# 8_ddr3_termination.net
KiCad netlist of a schematic drawn in Altium Designer
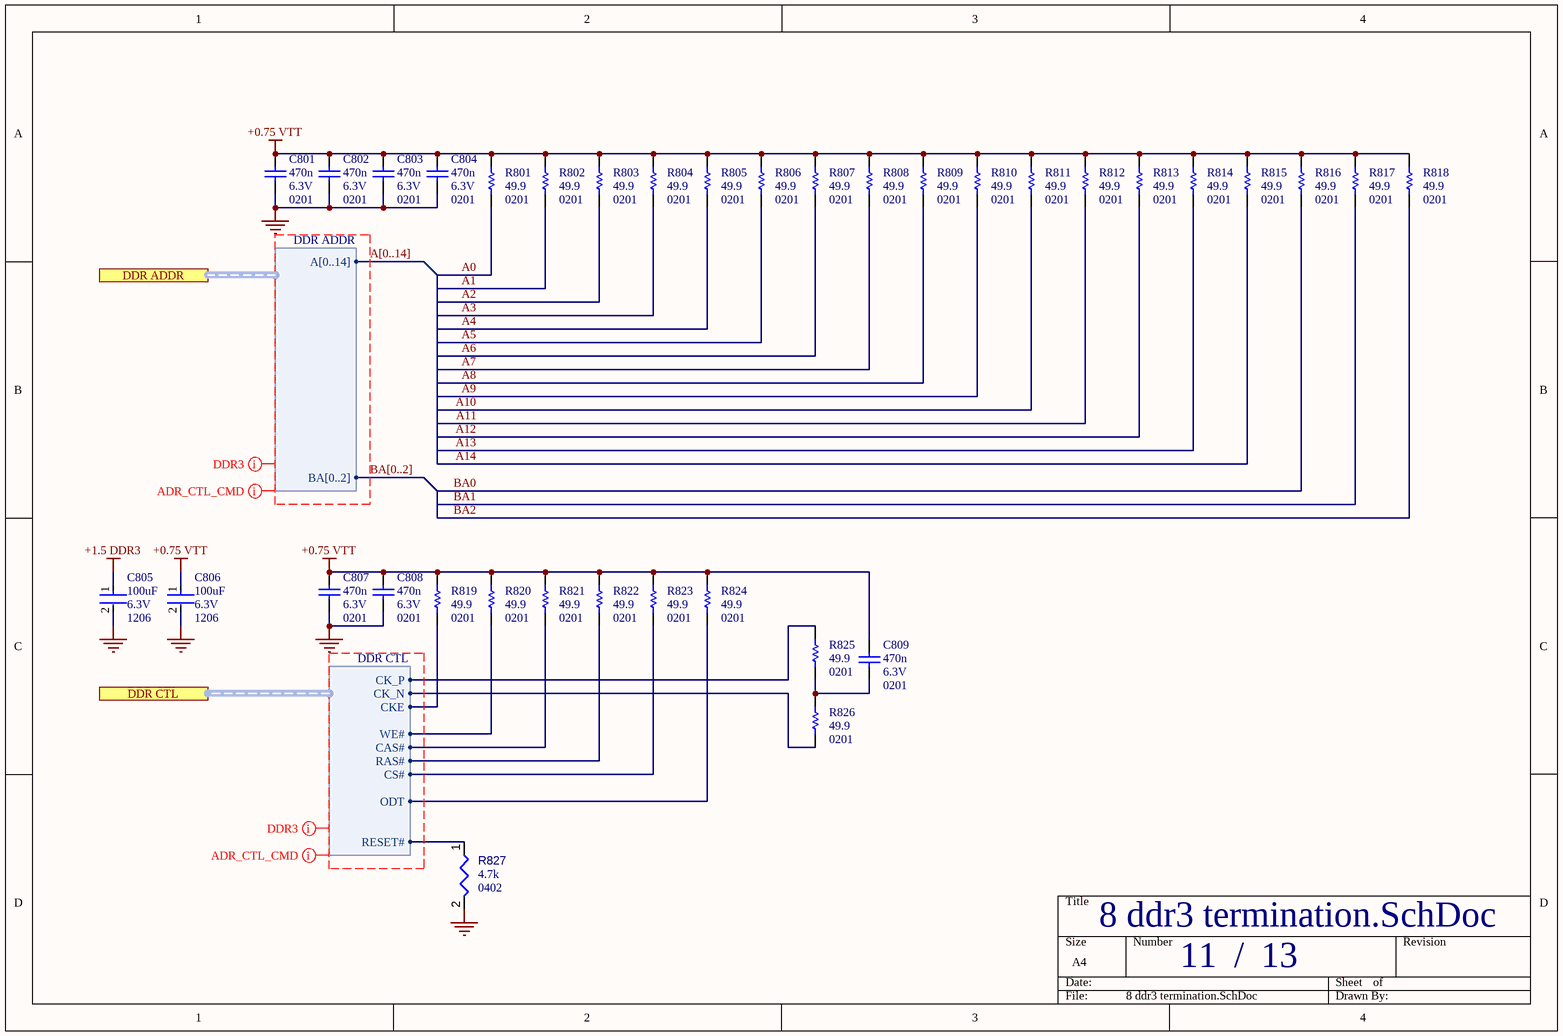
[diagram p0: 8 ddr3 termination.SchDoc]

(export (version "E")
  (design (tool "Eeschema 10.0.6"))
  (components
    (comp (ref "C801")
      (value "470n")
      (footprint "CAPC0603X33X15LL03T05")
      (fields
        (field (name "MANUFACTURER") "AVX Interconnect / Elco")
        (field (name "PART NUMBER") "02016D474KAT2A")
        (field (name "VOLTAGE RATING") "6.3V")
        (field (name "PACKAGE") "0201")
      )
      (libsource (lib "Altium Content Vault") (part "CAP"))
    )
    (comp (ref "C802")
      (value "470n")
      (footprint "CAPC0603X33X15LL03T05")
      (fields
        (field (name "MANUFACTURER") "AVX Interconnect / Elco")
        (field (name "PART NUMBER") "02016D474KAT2A")
        (field (name "VOLTAGE RATING") "6.3V")
        (field (name "PACKAGE") "0201")
      )
      (libsource (lib "Altium Content Vault") (part "CAP"))
    )
    (comp (ref "C803")
      (value "470n")
      (footprint "CAPC0603X33X15LL03T05")
      (fields
        (field (name "MANUFACTURER") "AVX Interconnect / Elco")
        (field (name "PART NUMBER") "02016D474KAT2A")
        (field (name "VOLTAGE RATING") "6.3V")
        (field (name "PACKAGE") "0201")
      )
      (libsource (lib "Altium Content Vault") (part "CAP"))
    )
    (comp (ref "C804")
      (value "470n")
      (footprint "CAPC0603X33X15LL03T05")
      (fields
        (field (name "MANUFACTURER") "AVX Interconnect / Elco")
        (field (name "PART NUMBER") "02016D474KAT2A")
        (field (name "VOLTAGE RATING") "6.3V")
        (field (name "PACKAGE") "0201")
      )
      (libsource (lib "Altium Content Vault") (part "CAP"))
    )
    (comp (ref "C805")
      (value "C1206C107M9PACTU")
      (footprint "FP-C1206C-EH-MFG")
      (description "CAP CER 100UF 6.3V X5R 1206")
      (fields
        (field (name "CASE CODE (IMPERIAL)") "1206")
        (field (name "VOLTAGE RATING (DC)") "6.3V")
        (field (name "TOLERANCE") "2%")
        (field (name "CAPACITANCE") "100uF")
        (field (name "VOLTAGE") "6.3V")
      )
      (libsource (lib "Altium Content Vault") (part "02cd4be3c70576c341d710602a673aa"))
    )
    (comp (ref "C806")
      (value "C1206C107M9PACTU")
      (footprint "FP-C1206C-EH-MFG")
      (description "CAP CER 100UF 6.3V X5R 1206")
      (fields
        (field (name "CASE CODE (IMPERIAL)") "1206")
        (field (name "VOLTAGE RATING (DC)") "6.3V")
        (field (name "TOLERANCE") "2%")
        (field (name "CAPACITANCE") "100uF")
        (field (name "VOLTAGE") "6.3V")
      )
      (libsource (lib "Altium Content Vault") (part "02cd4be3c70576c341d710602a673aa"))
    )
    (comp (ref "C807")
      (value "470n")
      (footprint "CAPC0603X33X15LL03T05")
      (fields
        (field (name "MANUFACTURER") "AVX Interconnect / Elco")
        (field (name "PART NUMBER") "02016D474KAT2A")
        (field (name "VOLTAGE RATING") "6.3V")
        (field (name "PACKAGE") "0201")
      )
      (libsource (lib "Altium Content Vault") (part "CAP"))
    )
    (comp (ref "C808")
      (value "470n")
      (footprint "CAPC0603X33X15LL03T05")
      (fields
        (field (name "MANUFACTURER") "AVX Interconnect / Elco")
        (field (name "PART NUMBER") "02016D474KAT2A")
        (field (name "VOLTAGE RATING") "6.3V")
        (field (name "PACKAGE") "0201")
      )
      (libsource (lib "Altium Content Vault") (part "CAP"))
    )
    (comp (ref "C809")
      (value "470n")
      (footprint "CAPC0603X33X15LL03T05")
      (fields
        (field (name "MANUFACTURER") "AVX Interconnect / Elco")
        (field (name "PART NUMBER") "02016D474KAT2A")
        (field (name "VOLTAGE RATING") "6.3V")
        (field (name "PACKAGE") "0201")
      )
      (libsource (lib "Altium Content Vault") (part "CAP"))
    )
    (comp (ref "R801")
      (value "49.9")
      (footprint "RESC0603X28X15LL05T05")
      (fields
        (field (name "MANUFACTURER") "Vishay Dale")
        (field (name "PART NUMBER") "CRCW020149R9FKED")
        (field (name "PACKAGE") "0201")
      )
      (libsource (lib "Altium Content Vault") (part "RES"))
    )
    (comp (ref "R802")
      (value "49.9")
      (footprint "RESC0603X28X15LL05T05")
      (fields
        (field (name "MANUFACTURER") "Vishay Dale")
        (field (name "PART NUMBER") "CRCW020149R9FKED")
        (field (name "PACKAGE") "0201")
      )
      (libsource (lib "Altium Content Vault") (part "RES"))
    )
    (comp (ref "R803")
      (value "49.9")
      (footprint "RESC0603X28X15LL05T05")
      (fields
        (field (name "MANUFACTURER") "Vishay Dale")
        (field (name "PART NUMBER") "CRCW020149R9FKED")
        (field (name "PACKAGE") "0201")
      )
      (libsource (lib "Altium Content Vault") (part "RES"))
    )
    (comp (ref "R804")
      (value "49.9")
      (footprint "RESC0603X28X15LL05T05")
      (fields
        (field (name "MANUFACTURER") "Vishay Dale")
        (field (name "PART NUMBER") "CRCW020149R9FKED")
        (field (name "PACKAGE") "0201")
      )
      (libsource (lib "Altium Content Vault") (part "RES"))
    )
    (comp (ref "R805")
      (value "49.9")
      (footprint "RESC0603X28X15LL05T05")
      (fields
        (field (name "MANUFACTURER") "Vishay Dale")
        (field (name "PART NUMBER") "CRCW020149R9FKED")
        (field (name "PACKAGE") "0201")
      )
      (libsource (lib "Altium Content Vault") (part "RES"))
    )
    (comp (ref "R806")
      (value "49.9")
      (footprint "RESC0603X28X15LL05T05")
      (fields
        (field (name "MANUFACTURER") "Vishay Dale")
        (field (name "PART NUMBER") "CRCW020149R9FKED")
        (field (name "PACKAGE") "0201")
      )
      (libsource (lib "Altium Content Vault") (part "RES"))
    )
    (comp (ref "R807")
      (value "49.9")
      (footprint "RESC0603X28X15LL05T05")
      (fields
        (field (name "MANUFACTURER") "Vishay Dale")
        (field (name "PART NUMBER") "CRCW020149R9FKED")
        (field (name "PACKAGE") "0201")
      )
      (libsource (lib "Altium Content Vault") (part "RES"))
    )
    (comp (ref "R808")
      (value "49.9")
      (footprint "RESC0603X28X15LL05T05")
      (fields
        (field (name "MANUFACTURER") "Vishay Dale")
        (field (name "PART NUMBER") "CRCW020149R9FKED")
        (field (name "PACKAGE") "0201")
      )
      (libsource (lib "Altium Content Vault") (part "RES"))
    )
    (comp (ref "R809")
      (value "49.9")
      (footprint "RESC0603X28X15LL05T05")
      (fields
        (field (name "MANUFACTURER") "Vishay Dale")
        (field (name "PART NUMBER") "CRCW020149R9FKED")
        (field (name "PACKAGE") "0201")
      )
      (libsource (lib "Altium Content Vault") (part "RES"))
    )
    (comp (ref "R810")
      (value "49.9")
      (footprint "RESC0603X28X15LL05T05")
      (fields
        (field (name "MANUFACTURER") "Vishay Dale")
        (field (name "PART NUMBER") "CRCW020149R9FKED")
        (field (name "PACKAGE") "0201")
      )
      (libsource (lib "Altium Content Vault") (part "RES"))
    )
    (comp (ref "R811")
      (value "49.9")
      (footprint "RESC0603X28X15LL05T05")
      (fields
        (field (name "MANUFACTURER") "Vishay Dale")
        (field (name "PART NUMBER") "CRCW020149R9FKED")
        (field (name "PACKAGE") "0201")
      )
      (libsource (lib "Altium Content Vault") (part "RES"))
    )
    (comp (ref "R812")
      (value "49.9")
      (footprint "RESC0603X28X15LL05T05")
      (fields
        (field (name "MANUFACTURER") "Vishay Dale")
        (field (name "PART NUMBER") "CRCW020149R9FKED")
        (field (name "PACKAGE") "0201")
      )
      (libsource (lib "Altium Content Vault") (part "RES"))
    )
    (comp (ref "R813")
      (value "49.9")
      (footprint "RESC0603X28X15LL05T05")
      (fields
        (field (name "MANUFACTURER") "Vishay Dale")
        (field (name "PART NUMBER") "CRCW020149R9FKED")
        (field (name "PACKAGE") "0201")
      )
      (libsource (lib "Altium Content Vault") (part "RES"))
    )
    (comp (ref "R814")
      (value "49.9")
      (footprint "RESC0603X28X15LL05T05")
      (fields
        (field (name "MANUFACTURER") "Vishay Dale")
        (field (name "PART NUMBER") "CRCW020149R9FKED")
        (field (name "PACKAGE") "0201")
      )
      (libsource (lib "Altium Content Vault") (part "RES"))
    )
    (comp (ref "R815")
      (value "49.9")
      (footprint "RESC0603X28X15LL05T05")
      (fields
        (field (name "MANUFACTURER") "Vishay Dale")
        (field (name "PART NUMBER") "CRCW020149R9FKED")
        (field (name "PACKAGE") "0201")
      )
      (libsource (lib "Altium Content Vault") (part "RES"))
    )
    (comp (ref "R816")
      (value "49.9")
      (footprint "RESC0603X28X15LL05T05")
      (fields
        (field (name "MANUFACTURER") "Vishay Dale")
        (field (name "PART NUMBER") "CRCW020149R9FKED")
        (field (name "PACKAGE") "0201")
      )
      (libsource (lib "Altium Content Vault") (part "RES"))
    )
    (comp (ref "R817")
      (value "49.9")
      (footprint "RESC0603X28X15LL05T05")
      (fields
        (field (name "MANUFACTURER") "Vishay Dale")
        (field (name "PART NUMBER") "CRCW020149R9FKED")
        (field (name "PACKAGE") "0201")
      )
      (libsource (lib "Altium Content Vault") (part "RES"))
    )
    (comp (ref "R818")
      (value "49.9")
      (footprint "RESC0603X28X15LL05T05")
      (fields
        (field (name "MANUFACTURER") "Vishay Dale")
        (field (name "PART NUMBER") "CRCW020149R9FKED")
        (field (name "PACKAGE") "0201")
      )
      (libsource (lib "Altium Content Vault") (part "RES"))
    )
    (comp (ref "R819")
      (value "49.9")
      (footprint "RESC0603X28X15LL05T05")
      (fields
        (field (name "MANUFACTURER") "Vishay Dale")
        (field (name "PART NUMBER") "CRCW020149R9FKED")
        (field (name "PACKAGE") "0201")
      )
      (libsource (lib "Altium Content Vault") (part "RES"))
    )
    (comp (ref "R820")
      (value "49.9")
      (footprint "RESC0603X28X15LL05T05")
      (fields
        (field (name "MANUFACTURER") "Vishay Dale")
        (field (name "PART NUMBER") "CRCW020149R9FKED")
        (field (name "PACKAGE") "0201")
      )
      (libsource (lib "Altium Content Vault") (part "RES"))
    )
    (comp (ref "R821")
      (value "49.9")
      (footprint "RESC0603X28X15LL05T05")
      (fields
        (field (name "MANUFACTURER") "Vishay Dale")
        (field (name "PART NUMBER") "CRCW020149R9FKED")
        (field (name "PACKAGE") "0201")
      )
      (libsource (lib "Altium Content Vault") (part "RES"))
    )
    (comp (ref "R822")
      (value "49.9")
      (footprint "RESC0603X28X15LL05T05")
      (fields
        (field (name "MANUFACTURER") "Vishay Dale")
        (field (name "PART NUMBER") "CRCW020149R9FKED")
        (field (name "PACKAGE") "0201")
      )
      (libsource (lib "Altium Content Vault") (part "RES"))
    )
    (comp (ref "R823")
      (value "49.9")
      (footprint "RESC0603X28X15LL05T05")
      (fields
        (field (name "MANUFACTURER") "Vishay Dale")
        (field (name "PART NUMBER") "CRCW020149R9FKED")
        (field (name "PACKAGE") "0201")
      )
      (libsource (lib "Altium Content Vault") (part "RES"))
    )
    (comp (ref "R824")
      (value "49.9")
      (footprint "RESC0603X28X15LL05T05")
      (fields
        (field (name "MANUFACTURER") "Vishay Dale")
        (field (name "PART NUMBER") "CRCW020149R9FKED")
        (field (name "PACKAGE") "0201")
      )
      (libsource (lib "Altium Content Vault") (part "RES"))
    )
    (comp (ref "R825")
      (value "49.9")
      (footprint "RESC0603X28X15LL05T05")
      (fields
        (field (name "MANUFACTURER") "Vishay Dale")
        (field (name "PART NUMBER") "CRCW020149R9FKED")
        (field (name "PACKAGE") "0201")
      )
      (libsource (lib "Altium Content Vault") (part "RES"))
    )
    (comp (ref "R826")
      (value "49.9")
      (footprint "RESC0603X28X15LL05T05")
      (fields
        (field (name "MANUFACTURER") "Vishay Dale")
        (field (name "PART NUMBER") "CRCW020149R9FKED")
        (field (name "PACKAGE") "0201")
      )
      (libsource (lib "Altium Content Vault") (part "RES"))
    )
    (comp (ref "R827")
      (value "4.7k")
      (footprint "RESC0402(1005)_L")
      (description "Resistor")
      (fields (field (name "CASE/PACKAGE") "0402") (field (name "Comment") "Resistors,0402,4.7k"))
      (libsource (lib "UBC Uncrewed Aircraft Systems") (part "RES-2"))
    )
  )
  (nets
    (net (code "4") (name "+0.75 VTT") (class "Default")
      (node (ref "C801") (pin "1") (pinfunction "1_1") (pintype "passive"))
      (node (ref "C802") (pin "1") (pinfunction "1_1") (pintype "passive"))
      (node (ref "C803") (pin "1") (pinfunction "1_1") (pintype "passive"))
      (node (ref "C804") (pin "1") (pinfunction "1_1") (pintype "passive"))
      (node (ref "C806") (pin "1") (pinfunction "1_1") (pintype "passive"))
      (node (ref "C807") (pin "1") (pinfunction "1_1") (pintype "passive"))
      (node (ref "C808") (pin "1") (pinfunction "1_1") (pintype "passive"))
      (node (ref "C809") (pin "1") (pinfunction "1_1") (pintype "passive"))
      (node (ref "R801") (pin "2") (pinfunction "2_2") (pintype "passive"))
      (node (ref "R802") (pin "2") (pinfunction "2_2") (pintype "passive"))
      (node (ref "R803") (pin "2") (pinfunction "2_2") (pintype "passive"))
      (node (ref "R804") (pin "2") (pinfunction "2_2") (pintype "passive"))
      (node (ref "R805") (pin "2") (pinfunction "2_2") (pintype "passive"))
      (node (ref "R806") (pin "2") (pinfunction "2_2") (pintype "passive"))
      (node (ref "R807") (pin "2") (pinfunction "2_2") (pintype "passive"))
      (node (ref "R808") (pin "2") (pinfunction "2_2") (pintype "passive"))
      (node (ref "R809") (pin "2") (pinfunction "2_2") (pintype "passive"))
      (node (ref "R810") (pin "2") (pinfunction "2_2") (pintype "passive"))
      (node (ref "R811") (pin "2") (pinfunction "2_2") (pintype "passive"))
      (node (ref "R812") (pin "2") (pinfunction "2_2") (pintype "passive"))
      (node (ref "R813") (pin "2") (pinfunction "2_2") (pintype "passive"))
      (node (ref "R814") (pin "2") (pinfunction "2_2") (pintype "passive"))
      (node (ref "R815") (pin "2") (pinfunction "2_2") (pintype "passive"))
      (node (ref "R816") (pin "2") (pinfunction "2_2") (pintype "passive"))
      (node (ref "R817") (pin "2") (pinfunction "2_2") (pintype "passive"))
      (node (ref "R818") (pin "2") (pinfunction "2_2") (pintype "passive"))
      (node (ref "R819") (pin "2") (pinfunction "2_2") (pintype "passive"))
      (node (ref "R820") (pin "2") (pinfunction "2_2") (pintype "passive"))
      (node (ref "R821") (pin "2") (pinfunction "2_2") (pintype "passive"))
      (node (ref "R822") (pin "2") (pinfunction "2_2") (pintype "passive"))
      (node (ref "R823") (pin "2") (pinfunction "2_2") (pintype "passive"))
      (node (ref "R824") (pin "2") (pinfunction "2_2") (pintype "passive"))
    )
    (net (code "5") (name "+1.5 DDR3") (class "Default")
      (node (ref "C805") (pin "1") (pinfunction "1_1") (pintype "passive"))
    )
    (net (code "6") (name "/A0") (class "Default")
      (node (ref "R801") (pin "1") (pinfunction "1_1") (pintype "passive"))
    )
    (net (code "7") (name "/A1") (class "Default")
      (node (ref "R802") (pin "1") (pinfunction "1_1") (pintype "passive"))
    )
    (net (code "8") (name "/A2") (class "Default")
      (node (ref "R803") (pin "1") (pinfunction "1_1") (pintype "passive"))
    )
    (net (code "9") (name "/A3") (class "Default")
      (node (ref "R804") (pin "1") (pinfunction "1_1") (pintype "passive"))
    )
    (net (code "10") (name "/A4") (class "Default")
      (node (ref "R805") (pin "1") (pinfunction "1_1") (pintype "passive"))
    )
    (net (code "11") (name "/A5") (class "Default")
      (node (ref "R806") (pin "1") (pinfunction "1_1") (pintype "passive"))
    )
    (net (code "12") (name "/A6") (class "Default")
      (node (ref "R807") (pin "1") (pinfunction "1_1") (pintype "passive"))
    )
    (net (code "13") (name "/A7") (class "Default")
      (node (ref "R808") (pin "1") (pinfunction "1_1") (pintype "passive"))
    )
    (net (code "14") (name "/A8") (class "Default")
      (node (ref "R809") (pin "1") (pinfunction "1_1") (pintype "passive"))
    )
    (net (code "15") (name "/A9") (class "Default")
      (node (ref "R810") (pin "1") (pinfunction "1_1") (pintype "passive"))
    )
    (net (code "16") (name "/A10") (class "Default")
      (node (ref "R811") (pin "1") (pinfunction "1_1") (pintype "passive"))
    )
    (net (code "17") (name "/A11") (class "Default")
      (node (ref "R812") (pin "1") (pinfunction "1_1") (pintype "passive"))
    )
    (net (code "18") (name "/A12") (class "Default")
      (node (ref "R813") (pin "1") (pinfunction "1_1") (pintype "passive"))
    )
    (net (code "19") (name "/A13") (class "Default")
      (node (ref "R814") (pin "1") (pinfunction "1_1") (pintype "passive"))
    )
    (net (code "20") (name "/A14") (class "Default")
      (node (ref "R815") (pin "1") (pinfunction "1_1") (pintype "passive"))
    )
    (net (code "22") (name "/BA0") (class "Default")
      (node (ref "R816") (pin "1") (pinfunction "1_1") (pintype "passive"))
    )
    (net (code "23") (name "/BA1") (class "Default")
      (node (ref "R817") (pin "1") (pinfunction "1_1") (pintype "passive"))
    )
    (net (code "24") (name "/BA2") (class "Default")
      (node (ref "R818") (pin "1") (pinfunction "1_1") (pintype "passive"))
    )
    (net (code "25") (name "/CAS#") (class "Default")
      (node (ref "R821") (pin "1") (pinfunction "1_1") (pintype "passive"))
    )
    (net (code "26") (name "/CKE") (class "Default")
      (node (ref "R819") (pin "1") (pinfunction "1_1") (pintype "passive"))
    )
    (net (code "27") (name "/CK_N") (class "Default")
      (node (ref "R826") (pin "1") (pinfunction "1_1") (pintype "passive"))
    )
    (net (code "28") (name "/CK_P") (class "Default")
      (node (ref "R825") (pin "2") (pinfunction "2_2") (pintype "passive"))
    )
    (net (code "29") (name "/CS#") (class "Default")
      (node (ref "R823") (pin "1") (pinfunction "1_1") (pintype "passive"))
    )
    (net (code "31") (name "/ODT") (class "Default")
      (node (ref "R824") (pin "1") (pinfunction "1_1") (pintype "passive"))
    )
    (net (code "32") (name "/RAS#") (class "Default")
      (node (ref "R822") (pin "1") (pinfunction "1_1") (pintype "passive"))
    )
    (net (code "33") (name "/RESET#") (class "Default")
      (node (ref "R827") (pin "1") (pinfunction "1_1") (pintype "passive"))
    )
    (net (code "34") (name "/WE#") (class "Default")
      (node (ref "R820") (pin "1") (pinfunction "1_1") (pintype "passive"))
    )
    (net (code "37") (name "GND") (class "Default")
      (node (ref "C801") (pin "2") (pinfunction "2_2") (pintype "passive"))
      (node (ref "C802") (pin "2") (pinfunction "2_2") (pintype "passive"))
      (node (ref "C803") (pin "2") (pinfunction "2_2") (pintype "passive"))
      (node (ref "C804") (pin "2") (pinfunction "2_2") (pintype "passive"))
      (node (ref "C805") (pin "2") (pinfunction "2_2") (pintype "passive"))
      (node (ref "C806") (pin "2") (pinfunction "2_2") (pintype "passive"))
      (node (ref "C807") (pin "2") (pinfunction "2_2") (pintype "passive"))
      (node (ref "C808") (pin "2") (pinfunction "2_2") (pintype "passive"))
      (node (ref "R827") (pin "2") (pinfunction "2_2") (pintype "passive"))
    )
    (net (code "38") (name "Net-(C809-Pad2)") (class "Default")
      (node (ref "C809") (pin "2") (pinfunction "2_2") (pintype "passive"))
      (node (ref "R825") (pin "1") (pinfunction "1_1") (pintype "passive"))
      (node (ref "R826") (pin "2") (pinfunction "2_2") (pintype "passive"))
    )
  )
)
